# Buggy_Motor_Board.net
KiCad netlist of a schematic drawn in EAGLE
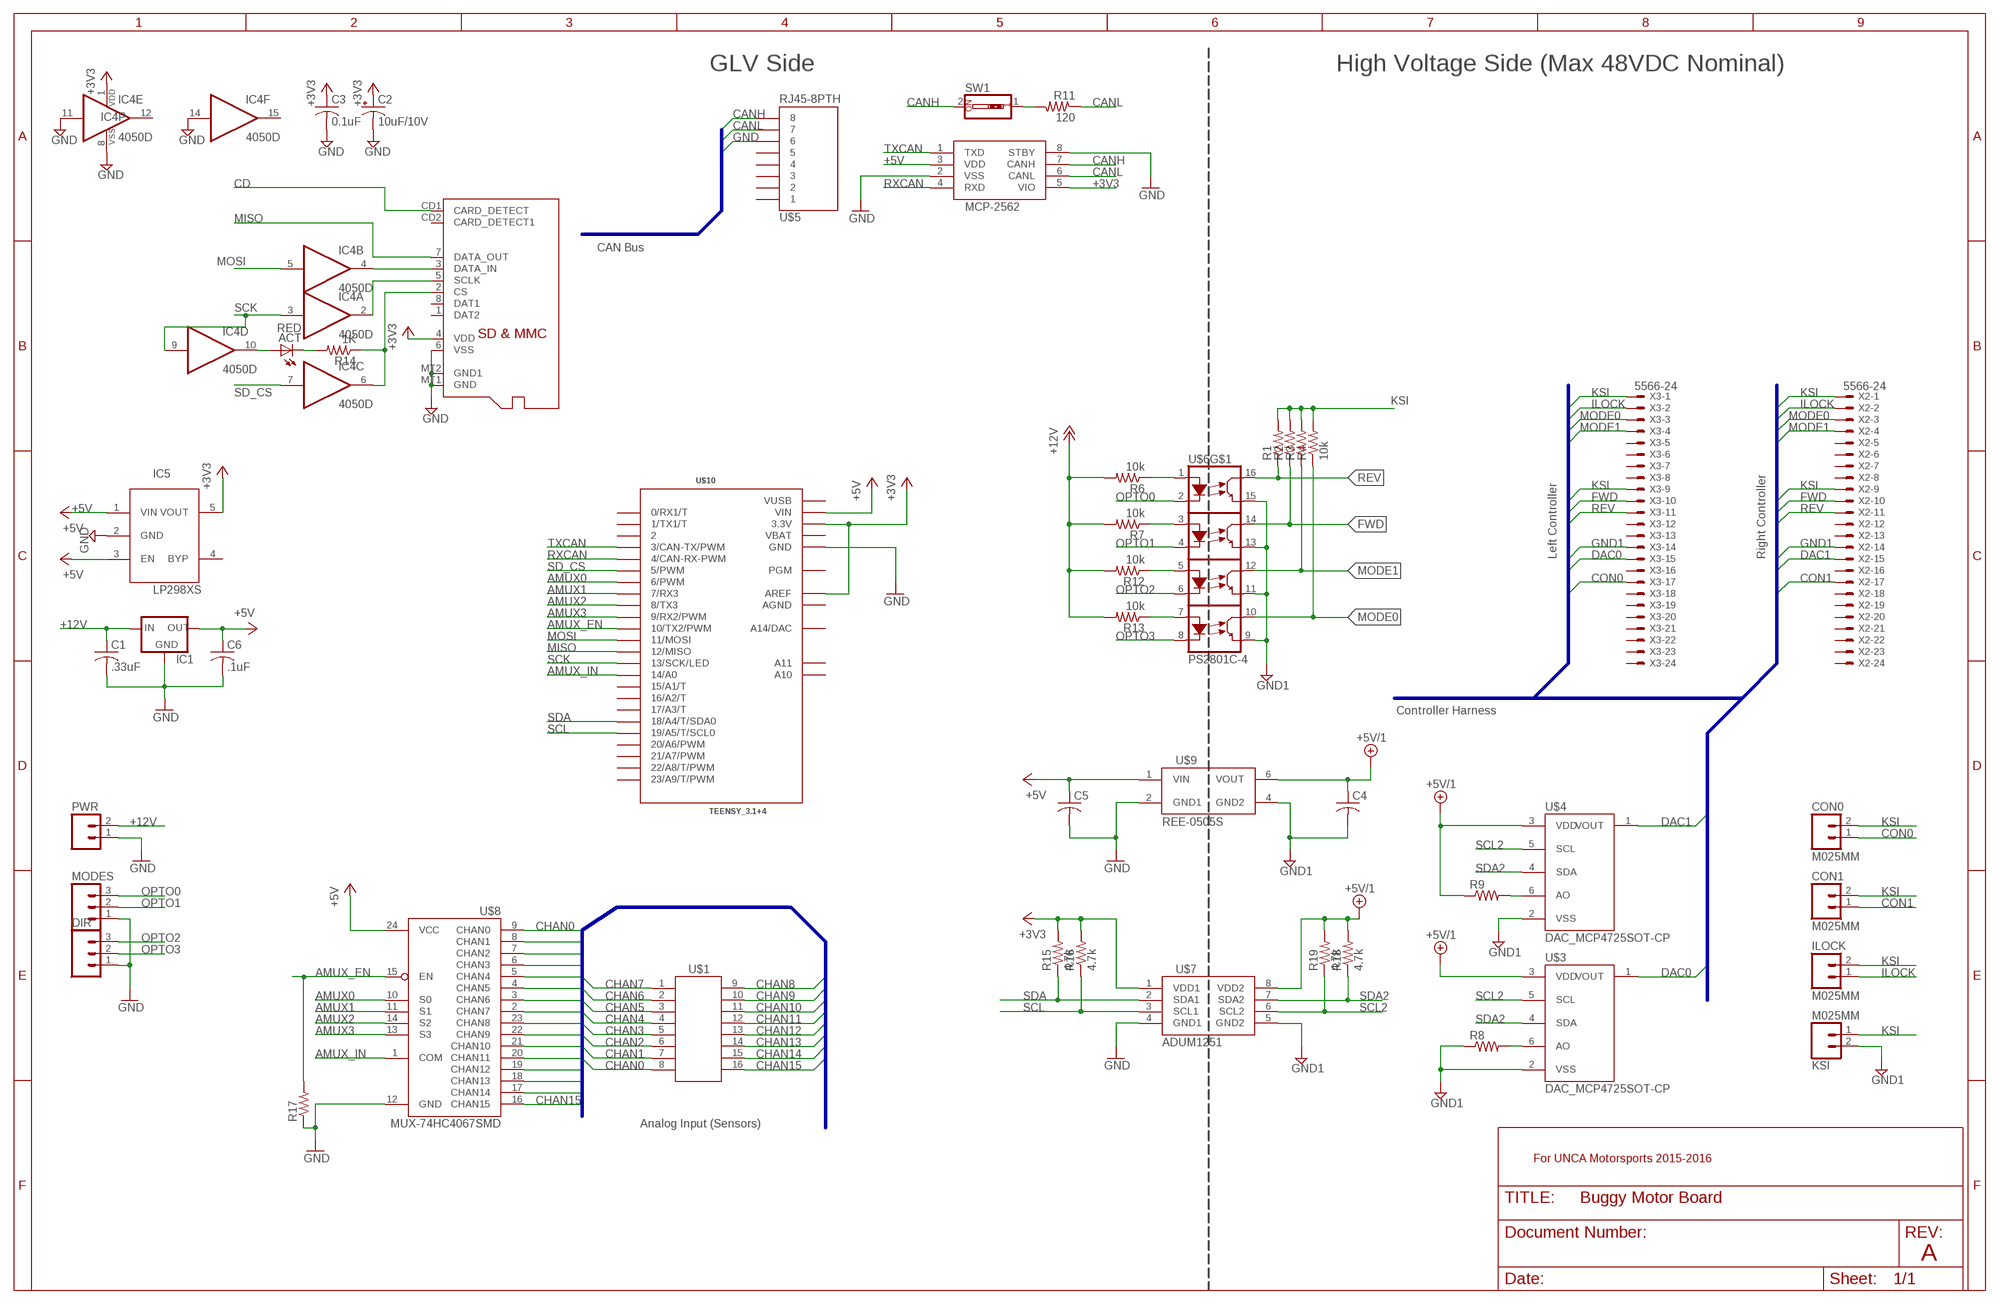
[diagram p0: schematic, sheet 1]

(export (version "E")
  (design (tool "Eeschema 10.0.6"))
  (components
    (comp (ref "ACT")
      (value "RED")
      (footprint "eagle-import:CHIP-LED0805")
      (libsource (lib "eagle-import") (part "LEDCHIP-LED0805"))
    )
    (comp (ref "C1")
      (value ".33uF")
      (footprint "eagle-import:C0805")
      (libsource (lib "eagle-import") (part "rcl_C-USC0805"))
    )
    (comp (ref "C2")
      (value "10uF/10V")
      (footprint "eagle-import:A_3216-18R")
      (libsource (lib "eagle-import") (part "CPOL-USA/3216-18R"))
    )
    (comp (ref "C3")
      (value "0.1uF")
      (footprint "eagle-import:C0805K")
      (libsource (lib "eagle-import") (part "C-USC0805K"))
    )
    (comp (ref "C4")
      (value "C-USC1210K")
      (footprint "eagle-import:C1210K")
      (libsource (lib "eagle-import") (part "rcl_C-USC1210K"))
    )
    (comp (ref "C5")
      (value "C-USC1210K")
      (footprint "eagle-import:C1210K")
      (libsource (lib "eagle-import") (part "rcl_C-USC1210K"))
    )
    (comp (ref "C6")
      (value ".1uF")
      (footprint "eagle-import:C0805")
      (libsource (lib "eagle-import") (part "rcl_C-USC0805"))
    )
    (comp (ref "CON0")
      (value "M025MM")
      (footprint "eagle-import:SCREWTERMINAL-5MM-2")
      (libsource (lib "eagle-import") (part "M025MM"))
    )
    (comp (ref "CON1")
      (value "M025MM")
      (footprint "eagle-import:SCREWTERMINAL-5MM-2")
      (libsource (lib "eagle-import") (part "M025MM"))
    )
    (comp (ref "DIR")
      (value "M03SCREW_LOCK")
      (footprint "eagle-import:SCREWTERMINAL-3.5MM-3_LOCK.007S")
      (libsource (lib "eagle-import") (part "M03SCREW_LOCK"))
    )
    (comp (ref "IC1")
      (value "V_REG_78XXSIDE")
      (footprint "eagle-import:78XXL")
      (libsource (lib "eagle-import") (part "V_REG_78XXSIDE"))
    )
    (comp (ref "IC4")
      (value "4050D")
      (footprint "eagle-import:SO16")
      (libsource (lib "eagle-import") (part "4050D"))
    )
    (comp (ref "IC5")
      (value "LP298XS")
      (footprint "eagle-import:SOT23-5L")
      (libsource (lib "eagle-import") (part "LP298XS"))
    )
    (comp (ref "ILOCK")
      (value "M025MM")
      (footprint "eagle-import:SCREWTERMINAL-5MM-2")
      (libsource (lib "eagle-import") (part "M025MM"))
    )
    (comp (ref "KSI")
      (value "M025MM")
      (footprint "eagle-import:SCREWTERMINAL-5MM-2")
      (libsource (lib "eagle-import") (part "M025MM"))
    )
    (comp (ref "MCP-2562")
      (value "MCP2562")
      (footprint "eagle-import:SO08")
      (libsource (lib "eagle-import") (part "MCP2562"))
    )
    (comp (ref "MODES")
      (value "M03SCREW_LOCK")
      (footprint "eagle-import:SCREWTERMINAL-3.5MM-3_LOCK.007S")
      (libsource (lib "eagle-import") (part "M03SCREW_LOCK"))
    )
    (comp (ref "PWR")
      (value "M023.5MM_LOCK")
      (footprint "eagle-import:SCREWTERMINAL-3.5MM-2_LOCK")
      (libsource (lib "eagle-import") (part "M023.5MM_LOCK"))
    )
    (comp (ref "R1")
      (value "RESISTOR0805-RES")
      (footprint "eagle-import:0805")
      (libsource (lib "eagle-import") (part "RESISTOR0805-RES"))
    )
    (comp (ref "R2")
      (value "RESISTOR0805-RES")
      (footprint "eagle-import:0805")
      (libsource (lib "eagle-import") (part "RESISTOR0805-RES"))
    )
    (comp (ref "R3")
      (value "RESISTOR0805-RES")
      (footprint "eagle-import:0805")
      (libsource (lib "eagle-import") (part "RESISTOR0805-RES"))
    )
    (comp (ref "R4")
      (value "10k")
      (footprint "eagle-import:0805")
      (libsource (lib "eagle-import") (part "RESISTOR0805-RES"))
    )
    (comp (ref "R6")
      (value "10k")
      (footprint "eagle-import:0805")
      (libsource (lib "eagle-import") (part "RESISTOR0805-RES"))
    )
    (comp (ref "R7")
      (value "10k")
      (footprint "eagle-import:0805")
      (libsource (lib "eagle-import") (part "RESISTOR0805-RES"))
    )
    (comp (ref "R8")
      (value "RESISTOR0805-RES")
      (footprint "eagle-import:0805")
      (libsource (lib "eagle-import") (part "RESISTOR0805-RES"))
    )
    (comp (ref "R9")
      (value "RESISTOR0805-RES")
      (footprint "eagle-import:0805")
      (libsource (lib "eagle-import") (part "RESISTOR0805-RES"))
    )
    (comp (ref "R11")
      (value "120")
      (footprint "eagle-import:0805")
      (libsource (lib "eagle-import") (part "RESISTOR0805-RES"))
    )
    (comp (ref "R12")
      (value "10k")
      (footprint "eagle-import:0805")
      (libsource (lib "eagle-import") (part "RESISTOR0805-RES"))
    )
    (comp (ref "R13")
      (value "10k")
      (footprint "eagle-import:0805")
      (libsource (lib "eagle-import") (part "RESISTOR0805-RES"))
    )
    (comp (ref "R14")
      (value "1K")
      (footprint "eagle-import:0805")
      (libsource (lib "eagle-import") (part "RESISTOR0805-RES"))
    )
    (comp (ref "R15")
      (value "4.7k")
      (footprint "eagle-import:0805")
      (libsource (lib "eagle-import") (part "RESISTOR0805-RES"))
    )
    (comp (ref "R16")
      (value "4.7k")
      (footprint "eagle-import:0805")
      (libsource (lib "eagle-import") (part "RESISTOR0805-RES"))
    )
    (comp (ref "R17")
      (value "RESISTOR0805-RES")
      (footprint "eagle-import:0805")
      (libsource (lib "eagle-import") (part "RESISTOR0805-RES"))
    )
    (comp (ref "R18")
      (value "4.7k")
      (footprint "eagle-import:0805")
      (libsource (lib "eagle-import") (part "RESISTOR0805-RES"))
    )
    (comp (ref "R19")
      (value "4.7k")
      (footprint "eagle-import:0805")
      (libsource (lib "eagle-import") (part "RESISTOR0805-RES"))
    )
    (comp (ref "SW1")
      (value "SW_DIP-1")
      (footprint "eagle-import:EDG-01")
      (libsource (lib "eagle-import") (part "SW_DIP-1"))
    )
    (comp (ref "U$1")
      (value "WM9300")
      (footprint "eagle-import:WM9300")
      (libsource (lib "eagle-import") (part "WM9300"))
    )
    (comp (ref "U$3")
      (value "DAC_MCP4725SOT-CP")
      (footprint "eagle-import:SOT23-6-MCP4725")
      (libsource (lib "eagle-import") (part "DAC_MCP4725SOT-CP"))
    )
    (comp (ref "U$4")
      (value "DAC_MCP4725SOT-CP")
      (footprint "eagle-import:SOT23-6-MCP4725")
      (libsource (lib "eagle-import") (part "DAC_MCP4725SOT-CP"))
    )
    (comp (ref "U$5")
      (value "RJ45-8PTH")
      (footprint "eagle-import:RJ45-8")
      (libsource (lib "eagle-import") (part "RJ45-8PTH"))
    )
    (comp (ref "U$6")
      (value "PS2801C-4")
      (footprint "eagle-import:16-SOIC")
      (libsource (lib "eagle-import") (part "PS2801C-4"))
    )
    (comp (ref "U$7")
      (value "ADUM1251")
      (footprint "eagle-import:8-SOIC")
      (libsource (lib "eagle-import") (part "ADUM1251"))
    )
    (comp (ref "U$8")
      (value "MUX-74HC4067SMD")
      (footprint "eagle-import:SSOP24")
      (libsource (lib "eagle-import") (part "MUX-74HC4067SMD"))
    )
    (comp (ref "U$9")
      (value "REE-0505S")
      (footprint "eagle-import:REE-0505S")
      (libsource (lib "eagle-import") (part "REE-0505S"))
    )
    (comp (ref "U$10")
      (value "TEENSY_3.1+4")
      (footprint "eagle-import:TEENSY_3.1+4")
      (libsource (lib "eagle-import") (part "TEENSY_3.1+4"))
    )
    (comp (ref "X1")
      (value "MICROSD")
      (footprint "eagle-import:MICROSD")
      (libsource (lib "eagle-import") (part "MICROSD"))
    )
    (comp (ref "X2")
      (value "5566-24")
      (footprint "eagle-import:5566-24")
      (libsource (lib "eagle-import") (part "5566-24"))
    )
    (comp (ref "X3")
      (value "5566-24")
      (footprint "eagle-import:5566-24")
      (libsource (lib "eagle-import") (part "5566-24"))
    )
  )
  (nets
    (net (code "1") (name "+3V3") (class "Default")
      (node (ref "C2") (pin "+") (pinfunction "+_+") (pintype "passive"))
      (node (ref "C3") (pin "1") (pinfunction "1_1") (pintype "passive"))
      (node (ref "IC4") (pin "1") (pinfunction "VDD_1") (pintype "power_in"))
      (node (ref "IC5") (pin "5") (pinfunction "VOUT_5") (pintype "bidirectional"))
      (node (ref "MCP-2562") (pin "5") (pinfunction "VIO_5") (pintype "bidirectional"))
      (node (ref "R15") (pin "2") (pinfunction "2_2") (pintype "passive"))
      (node (ref "R16") (pin "2") (pinfunction "2_2") (pintype "passive"))
      (node (ref "U$10") (pin "3.3V") (pinfunction "3.3V_3.3V") (pintype "power_in"))
      (node (ref "U$10") (pin "3.3V1") (pinfunction "3.3V_3.3V1") (pintype "power_in"))
      (node (ref "U$10") (pin "AREF") (pinfunction "AREF_AREF") (pintype "power_in"))
      (node (ref "U$7") (pin "1") (pinfunction "VDD1_1") (pintype "bidirectional"))
      (node (ref "X1") (pin "4") (pinfunction "VDD_4") (pintype "power_in"))
    )
    (net (code "2") (name "+5V") (class "Default")
      (node (ref "C5") (pin "1") (pinfunction "1_1") (pintype "passive"))
      (node (ref "C6") (pin "1") (pinfunction "1_1") (pintype "passive"))
      (node (ref "IC1") (pin "OUT") (pinfunction "OUT_OUT") (pintype "output"))
      (node (ref "IC5") (pin "1") (pinfunction "VIN_1") (pintype "bidirectional"))
      (node (ref "IC5") (pin "3") (pinfunction "EN_3") (pintype "bidirectional"))
      (node (ref "MCP-2562") (pin "3") (pinfunction "VDD_3") (pintype "bidirectional"))
      (node (ref "U$10") (pin "VIN") (pinfunction "VIN_VIN") (pintype "power_in"))
      (node (ref "U$8") (pin "24") (pinfunction "VCC_24") (pintype "bidirectional"))
      (node (ref "U$9") (pin "1") (pinfunction "VIN_1") (pintype "bidirectional"))
    )
    (net (code "3") (name "+5V{slash}1") (class "Default")
      (node (ref "C4") (pin "1") (pinfunction "1_1") (pintype "passive"))
      (node (ref "R18") (pin "2") (pinfunction "2_2") (pintype "passive"))
      (node (ref "R19") (pin "2") (pinfunction "2_2") (pintype "passive"))
      (node (ref "R9") (pin "1") (pinfunction "1_1") (pintype "passive"))
      (node (ref "U$3") (pin "3") (pinfunction "VDD_3") (pintype "bidirectional"))
      (node (ref "U$4") (pin "3") (pinfunction "VDD_3") (pintype "bidirectional"))
      (node (ref "U$7") (pin "8") (pinfunction "VDD2_8") (pintype "bidirectional"))
      (node (ref "U$9") (pin "6") (pinfunction "VOUT_6") (pintype "bidirectional"))
    )
    (net (code "4") (name "+12V") (class "Default")
      (node (ref "C1") (pin "1") (pinfunction "1_1") (pintype "passive"))
      (node (ref "IC1") (pin "IN") (pinfunction "IN_IN") (pintype "input"))
      (node (ref "PWR") (pin "2") (pinfunction "2_2") (pintype "passive"))
      (node (ref "R12") (pin "2") (pinfunction "2_2") (pintype "passive"))
      (node (ref "R13") (pin "2") (pinfunction "2_2") (pintype "passive"))
      (node (ref "R6") (pin "2") (pinfunction "2_2") (pintype "passive"))
      (node (ref "R7") (pin "2") (pinfunction "2_2") (pintype "passive"))
    )
    (net (code "5") (name "/AGND") (class "Default")
      (node (ref "U$10") (pin "AGND") (pinfunction "AGND_AGND") (pintype "power_in"))
    )
    (net (code "6") (name "/AMUX0") (class "Default")
      (node (ref "U$10") (pin "6") (pinfunction "6/PWM_6") (pintype "bidirectional"))
      (node (ref "U$8") (pin "10") (pinfunction "S0_10") (pintype "input"))
    )
    (net (code "7") (name "/AMUX1") (class "Default")
      (node (ref "U$10") (pin "7") (pinfunction "7/RX3_7") (pintype "bidirectional"))
      (node (ref "U$8") (pin "11") (pinfunction "S1_11") (pintype "input"))
    )
    (net (code "8") (name "/AMUX2") (class "Default")
      (node (ref "U$10") (pin "8") (pinfunction "8/TX3_8") (pintype "bidirectional"))
      (node (ref "U$8") (pin "14") (pinfunction "S2_14") (pintype "input"))
    )
    (net (code "9") (name "/AMUX3") (class "Default")
      (node (ref "U$10") (pin "9") (pinfunction "9/RX2/PWM_9") (pintype "bidirectional"))
      (node (ref "U$8") (pin "13") (pinfunction "S3_13") (pintype "input"))
    )
    (net (code "10") (name "/AMUX_EN") (class "Default")
      (node (ref "R17") (pin "2") (pinfunction "2_2") (pintype "passive"))
      (node (ref "U$10") (pin "10") (pinfunction "10/TX2/PWM_10") (pintype "bidirectional"))
      (node (ref "U$8") (pin "15") (pinfunction "EN_15") (pintype "input"))
    )
    (net (code "11") (name "/AMUX_IN") (class "Default")
      (node (ref "U$10") (pin "14/A0") (pinfunction "14/A0_14/A0") (pintype "bidirectional"))
      (node (ref "U$8") (pin "1") (pinfunction "COM_1") (pintype "bidirectional"))
    )
    (net (code "12") (name "/CANH") (class "Default")
      (node (ref "MCP-2562") (pin "7") (pinfunction "CANH_7") (pintype "bidirectional"))
      (node (ref "SW1") (pin "2") (pinfunction "2_2") (pintype "passive"))
      (node (ref "U$5") (pin "8") (pinfunction "8_8") (pintype "bidirectional"))
    )
    (net (code "13") (name "/CANL") (class "Default")
      (node (ref "MCP-2562") (pin "6") (pinfunction "CANL_6") (pintype "bidirectional"))
      (node (ref "R11") (pin "1") (pinfunction "1_1") (pintype "passive"))
      (node (ref "U$5") (pin "7") (pinfunction "7_7") (pintype "bidirectional"))
    )
    (net (code "14") (name "/CD") (class "Default")
      (node (ref "X1") (pin "CD1") (pinfunction "CARD_DETECT_CD1") (pintype "passive"))
    )
    (net (code "15") (name "/CHAN0") (class "Default")
      (node (ref "U$1") (pin "8") (pinfunction "P$8_8") (pintype "bidirectional"))
      (node (ref "U$8") (pin "9") (pinfunction "CHAN0_9") (pintype "bidirectional"))
    )
    (net (code "16") (name "/CHAN1") (class "Default")
      (node (ref "U$1") (pin "7") (pinfunction "P$7_7") (pintype "bidirectional"))
      (node (ref "U$8") (pin "8") (pinfunction "CHAN1_8") (pintype "bidirectional"))
    )
    (net (code "17") (name "/CHAN2") (class "Default")
      (node (ref "U$1") (pin "6") (pinfunction "P$6_6") (pintype "bidirectional"))
      (node (ref "U$8") (pin "7") (pinfunction "CHAN2_7") (pintype "bidirectional"))
    )
    (net (code "18") (name "/CHAN3") (class "Default")
      (node (ref "U$1") (pin "5") (pinfunction "P$5_5") (pintype "bidirectional"))
      (node (ref "U$8") (pin "6") (pinfunction "CHAN3_6") (pintype "bidirectional"))
    )
    (net (code "19") (name "/CHAN4") (class "Default")
      (node (ref "U$1") (pin "4") (pinfunction "P$4_4") (pintype "bidirectional"))
      (node (ref "U$8") (pin "5") (pinfunction "CHAN4_5") (pintype "bidirectional"))
    )
    (net (code "20") (name "/CHAN5") (class "Default")
      (node (ref "U$1") (pin "3") (pinfunction "P$3_3") (pintype "bidirectional"))
      (node (ref "U$8") (pin "4") (pinfunction "CHAN5_4") (pintype "bidirectional"))
    )
    (net (code "21") (name "/CHAN6") (class "Default")
      (node (ref "U$1") (pin "2") (pinfunction "P$2_2") (pintype "bidirectional"))
      (node (ref "U$8") (pin "3") (pinfunction "CHAN6_3") (pintype "bidirectional"))
    )
    (net (code "22") (name "/CHAN7") (class "Default")
      (node (ref "U$1") (pin "1") (pinfunction "P$1_1") (pintype "bidirectional"))
      (node (ref "U$8") (pin "2") (pinfunction "CHAN7_2") (pintype "bidirectional"))
    )
    (net (code "23") (name "/CHAN8") (class "Default")
      (node (ref "U$1") (pin "9") (pinfunction "P$9_9") (pintype "bidirectional"))
      (node (ref "U$8") (pin "23") (pinfunction "CHAN8_23") (pintype "bidirectional"))
    )
    (net (code "24") (name "/CHAN9") (class "Default")
      (node (ref "U$1") (pin "10") (pinfunction "P$10_10") (pintype "bidirectional"))
      (node (ref "U$8") (pin "22") (pinfunction "CHAN9_22") (pintype "bidirectional"))
    )
    (net (code "25") (name "/CHAN10") (class "Default")
      (node (ref "U$1") (pin "11") (pinfunction "P$11_11") (pintype "bidirectional"))
      (node (ref "U$8") (pin "21") (pinfunction "CHAN10_21") (pintype "bidirectional"))
    )
    (net (code "26") (name "/CHAN11") (class "Default")
      (node (ref "U$1") (pin "12") (pinfunction "P$12_12") (pintype "bidirectional"))
      (node (ref "U$8") (pin "20") (pinfunction "CHAN11_20") (pintype "bidirectional"))
    )
    (net (code "27") (name "/CHAN12") (class "Default")
      (node (ref "U$1") (pin "13") (pinfunction "P$13_13") (pintype "bidirectional"))
      (node (ref "U$8") (pin "19") (pinfunction "CHAN12_19") (pintype "bidirectional"))
    )
    (net (code "28") (name "/CHAN13") (class "Default")
      (node (ref "U$1") (pin "14") (pinfunction "P$14_14") (pintype "bidirectional"))
      (node (ref "U$8") (pin "18") (pinfunction "CHAN13_18") (pintype "bidirectional"))
    )
    (net (code "29") (name "/CHAN14") (class "Default")
      (node (ref "U$1") (pin "15") (pinfunction "P$15_15") (pintype "bidirectional"))
      (node (ref "U$8") (pin "17") (pinfunction "CHAN14_17") (pintype "bidirectional"))
    )
    (net (code "30") (name "/CHAN15") (class "Default")
      (node (ref "U$1") (pin "16") (pinfunction "P$16_16") (pintype "bidirectional"))
      (node (ref "U$8") (pin "16") (pinfunction "CHAN15_16") (pintype "bidirectional"))
    )
    (net (code "31") (name "/CON0") (class "Default")
      (node (ref "CON0") (pin "1") (pinfunction "1_1") (pintype "passive"))
      (node (ref "X3") (pin "17") (pinfunction "S_17") (pintype "passive"))
    )
    (net (code "32") (name "/CON1") (class "Default")
      (node (ref "CON1") (pin "1") (pinfunction "1_1") (pintype "passive"))
      (node (ref "X2") (pin "17") (pinfunction "S_17") (pintype "passive"))
    )
    (net (code "33") (name "/DAC0") (class "Default")
      (node (ref "U$3") (pin "1") (pinfunction "VOUT_1") (pintype "bidirectional"))
      (node (ref "X3") (pin "15") (pinfunction "S_15") (pintype "passive"))
    )
    (net (code "34") (name "/DAC1") (class "Default")
      (node (ref "U$4") (pin "1") (pinfunction "VOUT_1") (pintype "bidirectional"))
      (node (ref "X2") (pin "15") (pinfunction "S_15") (pintype "passive"))
    )
    (net (code "35") (name "/ILOCK") (class "Default")
      (node (ref "ILOCK") (pin "1") (pinfunction "1_1") (pintype "passive"))
      (node (ref "X2") (pin "2") (pinfunction "S_2") (pintype "passive"))
      (node (ref "X3") (pin "2") (pinfunction "S_2") (pintype "passive"))
    )
    (net (code "36") (name "/KSI") (class "Default")
      (node (ref "CON0") (pin "2") (pinfunction "2_2") (pintype "passive"))
      (node (ref "CON1") (pin "2") (pinfunction "2_2") (pintype "passive"))
      (node (ref "ILOCK") (pin "2") (pinfunction "2_2") (pintype "passive"))
      (node (ref "KSI") (pin "1") (pinfunction "1_1") (pintype "passive"))
      (node (ref "R1") (pin "2") (pinfunction "2_2") (pintype "passive"))
      (node (ref "R2") (pin "2") (pinfunction "2_2") (pintype "passive"))
      (node (ref "R3") (pin "2") (pinfunction "2_2") (pintype "passive"))
      (node (ref "R4") (pin "2") (pinfunction "2_2") (pintype "passive"))
      (node (ref "X2") (pin "1") (pinfunction "S_1") (pintype "passive"))
      (node (ref "X2") (pin "9") (pinfunction "S_9") (pintype "passive"))
      (node (ref "X3") (pin "1") (pinfunction "S_1") (pintype "passive"))
      (node (ref "X3") (pin "9") (pinfunction "S_9") (pintype "passive"))
    )
    (net (code "37") (name "/MISO") (class "Default")
      (node (ref "U$10") (pin "12") (pinfunction "12/MISO_12") (pintype "bidirectional"))
      (node (ref "X1") (pin "7") (pinfunction "DATA_OUT_7") (pintype "output"))
    )
    (net (code "38") (name "/MOSI") (class "Default")
      (node (ref "IC4") (pin "5") (pinfunction "I_5") (pintype "input"))
      (node (ref "U$10") (pin "11") (pinfunction "11/MOSI_11") (pintype "bidirectional"))
    )
    (net (code "39") (name "/OPTO0") (class "Default")
      (node (ref "MODES") (pin "3") (pinfunction "3_3") (pintype "passive"))
      (node (ref "U$6") (pin "2") (pinfunction "C_2") (pintype "passive"))
    )
    (net (code "40") (name "/OPTO1") (class "Default")
      (node (ref "MODES") (pin "2") (pinfunction "2_2") (pintype "passive"))
      (node (ref "U$6") (pin "4") (pinfunction "C_4") (pintype "passive"))
    )
    (net (code "41") (name "/OPTO2") (class "Default")
      (node (ref "DIR") (pin "3") (pinfunction "3_3") (pintype "passive"))
      (node (ref "U$6") (pin "6") (pinfunction "C_6") (pintype "passive"))
    )
    (net (code "42") (name "/OPTO3") (class "Default")
      (node (ref "DIR") (pin "2") (pinfunction "2_2") (pintype "passive"))
      (node (ref "U$6") (pin "8") (pinfunction "C_8") (pintype "passive"))
    )
    (net (code "43") (name "/RXCAN") (class "Default")
      (node (ref "MCP-2562") (pin "4") (pinfunction "RXD_4") (pintype "bidirectional"))
      (node (ref "U$10") (pin "4") (pinfunction "4/CAN-RX-PWM_4") (pintype "bidirectional"))
    )
    (net (code "44") (name "/SCK") (class "Default")
      (node (ref "IC4") (pin "3") (pinfunction "I_3") (pintype "input"))
      (node (ref "IC4") (pin "9") (pinfunction "I_9") (pintype "input"))
      (node (ref "U$10") (pin "13") (pinfunction "13/SCK/LED_13") (pintype "bidirectional"))
    )
    (net (code "45") (name "/SCL") (class "Default")
      (node (ref "R16") (pin "1") (pinfunction "1_1") (pintype "passive"))
      (node (ref "U$10") (pin "19/A5") (pinfunction "19/A5/T/SCL0_19/A5") (pintype "bidirectional"))
      (node (ref "U$7") (pin "3") (pinfunction "SCL1_3") (pintype "bidirectional"))
    )
    (net (code "46") (name "/SCL2") (class "Default")
      (node (ref "R19") (pin "1") (pinfunction "1_1") (pintype "passive"))
      (node (ref "U$3") (pin "5") (pinfunction "SCL_5") (pintype "bidirectional"))
      (node (ref "U$4") (pin "5") (pinfunction "SCL_5") (pintype "bidirectional"))
      (node (ref "U$7") (pin "6") (pinfunction "SCL2_6") (pintype "bidirectional"))
    )
    (net (code "47") (name "/SDA") (class "Default")
      (node (ref "R15") (pin "1") (pinfunction "1_1") (pintype "passive"))
      (node (ref "U$10") (pin "18/A4") (pinfunction "18/A4/T/SDA0_18/A4") (pintype "bidirectional"))
      (node (ref "U$7") (pin "2") (pinfunction "SDA1_2") (pintype "bidirectional"))
    )
    (net (code "48") (name "/SDA2") (class "Default")
      (node (ref "R18") (pin "1") (pinfunction "1_1") (pintype "passive"))
      (node (ref "U$3") (pin "4") (pinfunction "SDA_4") (pintype "bidirectional"))
      (node (ref "U$4") (pin "4") (pinfunction "SDA_4") (pintype "bidirectional"))
      (node (ref "U$7") (pin "7") (pinfunction "SDA2_7") (pintype "bidirectional"))
    )
    (net (code "49") (name "/SD_CS") (class "Default")
      (node (ref "IC4") (pin "7") (pinfunction "I_7") (pintype "input"))
      (node (ref "U$10") (pin "5") (pinfunction "5/PWM_5") (pintype "bidirectional"))
    )
    (net (code "50") (name "/TXCAN") (class "Default")
      (node (ref "MCP-2562") (pin "1") (pinfunction "TXD_1") (pintype "bidirectional"))
      (node (ref "U$10") (pin "3") (pinfunction "3/CAN-TX/PWM_3") (pintype "bidirectional"))
    )
    (net (code "51") (name "/VBAT") (class "Default")
      (node (ref "U$10") (pin "VBAT") (pinfunction "VBAT_VBAT") (pintype "power_in"))
    )
    (net (code "52") (name "/VUSB") (class "Default")
      (node (ref "U$10") (pin "VUSB") (pinfunction "VUSB_VUSB") (pintype "power_in"))
    )
    (net (code "53") (name "FWD") (class "Default")
      (node (ref "R2") (pin "1") (pinfunction "1_1") (pintype "passive"))
      (node (ref "U$6") (pin "14") (pinfunction "L1_14") (pintype "passive"))
      (node (ref "X2") (pin "10") (pinfunction "S_10") (pintype "passive"))
      (node (ref "X3") (pin "10") (pinfunction "S_10") (pintype "passive"))
    )
    (net (code "54") (name "GND") (class "Default")
      (node (ref "C1") (pin "2") (pinfunction "2_2") (pintype "passive"))
      (node (ref "C2") (pin "-") (pinfunction "-_-") (pintype "passive"))
      (node (ref "C3") (pin "2") (pinfunction "2_2") (pintype "passive"))
      (node (ref "C5") (pin "2") (pinfunction "2_2") (pintype "passive"))
      (node (ref "C6") (pin "2") (pinfunction "2_2") (pintype "passive"))
      (node (ref "DIR") (pin "1") (pinfunction "1_1") (pintype "passive"))
      (node (ref "IC1") (pin "GND") (pinfunction "GND_GND") (pintype "input"))
      (node (ref "IC4") (pin "11") (pinfunction "I_11") (pintype "input"))
      (node (ref "IC4") (pin "14") (pinfunction "I_14") (pintype "input"))
      (node (ref "IC4") (pin "8") (pinfunction "VSS_8") (pintype "power_in"))
      (node (ref "IC5") (pin "2") (pinfunction "GND_2") (pintype "bidirectional"))
      (node (ref "MCP-2562") (pin "2") (pinfunction "VSS_2") (pintype "bidirectional"))
      (node (ref "MCP-2562") (pin "8") (pinfunction "STBY_8") (pintype "bidirectional"))
      (node (ref "MODES") (pin "1") (pinfunction "1_1") (pintype "passive"))
      (node (ref "PWR") (pin "1") (pinfunction "1_1") (pintype "passive"))
      (node (ref "R17") (pin "1") (pinfunction "1_1") (pintype "passive"))
      (node (ref "U$10") (pin "GND") (pinfunction "GND_GND") (pintype "power_in"))
      (node (ref "U$10") (pin "GND1") (pinfunction "GND_GND1") (pintype "power_in"))
      (node (ref "U$5") (pin "6") (pinfunction "6_6") (pintype "bidirectional"))
      (node (ref "U$7") (pin "4") (pinfunction "GND1_4") (pintype "bidirectional"))
      (node (ref "U$8") (pin "12") (pinfunction "GND_12") (pintype "bidirectional"))
      (node (ref "U$9") (pin "2") (pinfunction "GND1_2") (pintype "bidirectional"))
      (node (ref "X1") (pin "6") (pinfunction "VSS_6") (pintype "power_in"))
      (node (ref "X1") (pin "MT1") (pinfunction "GND_MT1") (pintype "power_in"))
      (node (ref "X1") (pin "MT2") (pinfunction "GND1_MT2") (pintype "power_in"))
    )
    (net (code "55") (name "GND1") (class "Default")
      (node (ref "C4") (pin "2") (pinfunction "2_2") (pintype "passive"))
      (node (ref "KSI") (pin "2") (pinfunction "2_2") (pintype "passive"))
      (node (ref "R8") (pin "1") (pinfunction "1_1") (pintype "passive"))
      (node (ref "U$3") (pin "2") (pinfunction "VSS_2") (pintype "bidirectional"))
      (node (ref "U$4") (pin "2") (pinfunction "VSS_2") (pintype "bidirectional"))
      (node (ref "U$6") (pin "11") (pinfunction "L2_11") (pintype "passive"))
      (node (ref "U$6") (pin "13") (pinfunction "L2_13") (pintype "passive"))
      (node (ref "U$6") (pin "15") (pinfunction "L2_15") (pintype "passive"))
      (node (ref "U$6") (pin "9") (pinfunction "L2_9") (pintype "passive"))
      (node (ref "U$7") (pin "5") (pinfunction "GND2_5") (pintype "bidirectional"))
      (node (ref "U$9") (pin "4") (pinfunction "GND2_4") (pintype "bidirectional"))
      (node (ref "X2") (pin "14") (pinfunction "S_14") (pintype "passive"))
      (node (ref "X3") (pin "14") (pinfunction "S_14") (pintype "passive"))
    )
    (net (code "56") (name "MODE0") (class "Default")
      (node (ref "R4") (pin "1") (pinfunction "1_1") (pintype "passive"))
      (node (ref "U$6") (pin "10") (pinfunction "L1_10") (pintype "passive"))
      (node (ref "X2") (pin "3") (pinfunction "S_3") (pintype "passive"))
      (node (ref "X3") (pin "3") (pinfunction "S_3") (pintype "passive"))
    )
    (net (code "57") (name "MODE1") (class "Default")
      (node (ref "R3") (pin "1") (pinfunction "1_1") (pintype "passive"))
      (node (ref "U$6") (pin "12") (pinfunction "L1_12") (pintype "passive"))
      (node (ref "X2") (pin "4") (pinfunction "S_4") (pintype "passive"))
      (node (ref "X3") (pin "4") (pinfunction "S_4") (pintype "passive"))
    )
    (net (code "58") (name "Net-(ACT-PadC)") (class "Default")
      (node (ref "ACT") (pin "C") (pinfunction "C_C") (pintype "passive"))
      (node (ref "R14") (pin "2") (pinfunction "2_2") (pintype "passive"))
    )
    (net (code "59") (name "Net-(IC4A-O)") (class "Default")
      (node (ref "IC4") (pin "2") (pinfunction "O_2") (pintype "output"))
      (node (ref "X1") (pin "5") (pinfunction "SCLK_5") (pintype "input"))
    )
    (net (code "60") (name "Net-(IC4B-O)") (class "Default")
      (node (ref "IC4") (pin "4") (pinfunction "O_4") (pintype "output"))
      (node (ref "X1") (pin "3") (pinfunction "DATA_IN_3") (pintype "input"))
    )
    (net (code "61") (name "Net-(IC4C-O)") (class "Default")
      (node (ref "IC4") (pin "6") (pinfunction "O_6") (pintype "output"))
      (node (ref "R14") (pin "1") (pinfunction "1_1") (pintype "passive"))
      (node (ref "X1") (pin "2") (pinfunction "CS_2") (pintype "input"))
    )
    (net (code "62") (name "Net-(IC4D-O)") (class "Default")
      (node (ref "ACT") (pin "A") (pinfunction "A_A") (pintype "passive"))
      (node (ref "IC4") (pin "10") (pinfunction "O_10") (pintype "output"))
    )
    (net (code "63") (name "Net-(R11-Pad2)") (class "Default")
      (node (ref "R11") (pin "2") (pinfunction "2_2") (pintype "passive"))
      (node (ref "SW1") (pin "1") (pinfunction "1_1") (pintype "passive"))
    )
    (net (code "64") (name "Net-(U$3-AO)") (class "Default")
      (node (ref "R8") (pin "2") (pinfunction "2_2") (pintype "passive"))
      (node (ref "U$3") (pin "6") (pinfunction "AO_6") (pintype "bidirectional"))
    )
    (net (code "65") (name "Net-(U$4-AO)") (class "Default")
      (node (ref "R9") (pin "2") (pinfunction "2_2") (pintype "passive"))
      (node (ref "U$4") (pin "6") (pinfunction "AO_6") (pintype "bidirectional"))
    )
    (net (code "66") (name "Net-(U$6A-A)") (class "Default")
      (node (ref "R6") (pin "1") (pinfunction "1_1") (pintype "passive"))
      (node (ref "U$6") (pin "1") (pinfunction "A_1") (pintype "passive"))
    )
    (net (code "67") (name "Net-(U$6B-A)") (class "Default")
      (node (ref "R7") (pin "1") (pinfunction "1_1") (pintype "passive"))
      (node (ref "U$6") (pin "3") (pinfunction "A_3") (pintype "passive"))
    )
    (net (code "68") (name "Net-(U$6C-A)") (class "Default")
      (node (ref "R12") (pin "1") (pinfunction "1_1") (pintype "passive"))
      (node (ref "U$6") (pin "5") (pinfunction "A_5") (pintype "passive"))
    )
    (net (code "69") (name "Net-(U$6D-A)") (class "Default")
      (node (ref "R13") (pin "1") (pinfunction "1_1") (pintype "passive"))
      (node (ref "U$6") (pin "7") (pinfunction "A_7") (pintype "passive"))
    )
    (net (code "70") (name "REV") (class "Default")
      (node (ref "R1") (pin "1") (pinfunction "1_1") (pintype "passive"))
      (node (ref "U$6") (pin "16") (pinfunction "L1_16") (pintype "passive"))
      (node (ref "X2") (pin "11") (pinfunction "S_11") (pintype "passive"))
      (node (ref "X3") (pin "11") (pinfunction "S_11") (pintype "passive"))
    )
    (net (code "71") (name "unconnected-(IC4E-O-Pad12)") (class "Default")
      (node (ref "IC4") (pin "12") (pinfunction "O_12") (pintype "output"))
    )
    (net (code "72") (name "unconnected-(IC4F-O-Pad15)") (class "Default")
      (node (ref "IC4") (pin "15") (pinfunction "O_15") (pintype "output"))
    )
    (net (code "73") (name "unconnected-(IC5-BYP-Pad4)") (class "Default")
      (node (ref "IC5") (pin "4") (pinfunction "BYP_4") (pintype "bidirectional"))
    )
    (net (code "74") (name "unconnected-(U$5-Pad1)") (class "Default")
      (node (ref "U$5") (pin "1") (pinfunction "1_1") (pintype "bidirectional"))
    )
    (net (code "75") (name "unconnected-(U$5-Pad2)") (class "Default")
      (node (ref "U$5") (pin "2") (pinfunction "2_2") (pintype "bidirectional"))
    )
    (net (code "76") (name "unconnected-(U$5-Pad3)") (class "Default")
      (node (ref "U$5") (pin "3") (pinfunction "3_3") (pintype "bidirectional"))
    )
    (net (code "77") (name "unconnected-(U$5-Pad4)") (class "Default")
      (node (ref "U$5") (pin "4") (pinfunction "4_4") (pintype "bidirectional"))
    )
    (net (code "78") (name "unconnected-(U$5-Pad5)") (class "Default")
      (node (ref "U$5") (pin "5") (pinfunction "5_5") (pintype "bidirectional"))
    )
    (net (code "79") (name "unconnected-(U$10-0{slash}RX1{slash}T-Pad0)") (class "Default")
      (node (ref "U$10") (pin "0") (pinfunction "0/RX1/T_0") (pintype "bidirectional"))
    )
    (net (code "80") (name "unconnected-(U$10-1{slash}TX1{slash}T-Pad1)") (class "Default")
      (node (ref "U$10") (pin "1") (pinfunction "1/TX1/T_1") (pintype "bidirectional"))
    )
    (net (code "81") (name "unconnected-(U$10-15{slash}A1{slash}T-Pad15{slash}A1)") (class "Default")
      (node (ref "U$10") (pin "15/A1") (pinfunction "15/A1/T_15/A1") (pintype "bidirectional"))
    )
    (net (code "82") (name "unconnected-(U$10-16{slash}A2{slash}T-Pad16{slash}A2)") (class "Default")
      (node (ref "U$10") (pin "16/A2") (pinfunction "16/A2/T_16/A2") (pintype "bidirectional"))
    )
    (net (code "83") (name "unconnected-(U$10-17{slash}A3{slash}T-Pad17{slash}A3)") (class "Default")
      (node (ref "U$10") (pin "17/A3") (pinfunction "17/A3/T_17/A3") (pintype "bidirectional"))
    )
    (net (code "84") (name "unconnected-(U$10-20{slash}A6{slash}PWM-Pad20{slash}A6)") (class "Default")
      (node (ref "U$10") (pin "20/A6") (pinfunction "20/A6/PWM_20/A6") (pintype "bidirectional"))
    )
    (net (code "85") (name "unconnected-(U$10-21{slash}A7{slash}PWM-Pad21{slash}A7)") (class "Default")
      (node (ref "U$10") (pin "21/A7") (pinfunction "21/A7/PWM_21/A7") (pintype "bidirectional"))
    )
    (net (code "86") (name "unconnected-(U$10-22{slash}A8{slash}T{slash}PWM-Pad22{slash}A8)") (class "Default")
      (node (ref "U$10") (pin "22/A8") (pinfunction "22/A8/T/PWM_22/A8") (pintype "bidirectional"))
    )
    (net (code "87") (name "unconnected-(U$10-23{slash}A9{slash}T{slash}PWM-Pad23{slash}A9)") (class "Default")
      (node (ref "U$10") (pin "23/A9") (pinfunction "23/A9/T/PWM_23/A9") (pintype "bidirectional"))
    )
    (net (code "88") (name "unconnected-(U$10-A14{slash}DAC-PadA14)") (class "Default")
      (node (ref "U$10") (pin "A14") (pinfunction "A14/DAC_A14") (pintype "bidirectional"))
    )
    (net (code "89") (name "unconnected-(U$10-Pad2)") (class "Default")
      (node (ref "U$10") (pin "2") (pinfunction "2_2") (pintype "bidirectional"))
    )
    (net (code "90") (name "unconnected-(U$10-PadA10)") (class "Default")
      (node (ref "U$10") (pin "A10") (pinfunction "A10_A10") (pintype "bidirectional"))
    )
    (net (code "91") (name "unconnected-(U$10-PadA11)") (class "Default")
      (node (ref "U$10") (pin "A11") (pinfunction "A11_A11") (pintype "bidirectional"))
    )
    (net (code "92") (name "unconnected-(U$10-PadPGM)") (class "Default")
      (node (ref "U$10") (pin "PGM") (pinfunction "PGM_PGM") (pintype "bidirectional"))
    )
    (net (code "93") (name "unconnected-(X1-CARD_DETECT1-PadCD2)") (class "Default")
      (node (ref "X1") (pin "CD2") (pinfunction "CARD_DETECT1_CD2") (pintype "passive"))
    )
    (net (code "94") (name "unconnected-(X1-DAT1-Pad8)") (class "Default")
      (node (ref "X1") (pin "8") (pinfunction "DAT1_8") (pintype "bidirectional"))
    )
    (net (code "95") (name "unconnected-(X1-DAT2-Pad1)") (class "Default")
      (node (ref "X1") (pin "1") (pinfunction "DAT2_1") (pintype "bidirectional"))
    )
    (net (code "96") (name "unconnected-(X2D-S-Pad12)") (class "Default")
      (node (ref "X2") (pin "12") (pinfunction "S_12") (pintype "passive"))
    )
    (net (code "97") (name "unconnected-(X2E-S-Pad13)") (class "Default")
      (node (ref "X2") (pin "13") (pinfunction "S_13") (pintype "passive"))
    )
    (net (code "98") (name "unconnected-(X2H-S-Pad16)") (class "Default")
      (node (ref "X2") (pin "16") (pinfunction "S_16") (pintype "passive"))
    )
    (net (code "99") (name "unconnected-(X2J-S-Pad18)") (class "Default")
      (node (ref "X2") (pin "18") (pinfunction "S_18") (pintype "passive"))
    )
    (net (code "100") (name "unconnected-(X2K-S-Pad19)") (class "Default")
      (node (ref "X2") (pin "19") (pinfunction "S_19") (pintype "passive"))
    )
    (net (code "101") (name "unconnected-(X2M-S-Pad20)") (class "Default")
      (node (ref "X2") (pin "20") (pinfunction "S_20") (pintype "passive"))
    )
    (net (code "102") (name "unconnected-(X2N-S-Pad21)") (class "Default")
      (node (ref "X2") (pin "21") (pinfunction "S_21") (pintype "passive"))
    )
    (net (code "103") (name "unconnected-(X2O-S-Pad22)") (class "Default")
      (node (ref "X2") (pin "22") (pinfunction "S_22") (pintype "passive"))
    )
    (net (code "104") (name "unconnected-(X2P-S-Pad23)") (class "Default")
      (node (ref "X2") (pin "23") (pinfunction "S_23") (pintype "passive"))
    )
    (net (code "105") (name "unconnected-(X2Q-S-Pad24)") (class "Default")
      (node (ref "X2") (pin "24") (pinfunction "S_24") (pintype "passive"))
    )
    (net (code "106") (name "unconnected-(X2T-S-Pad5)") (class "Default")
      (node (ref "X2") (pin "5") (pinfunction "S_5") (pintype "passive"))
    )
    (net (code "107") (name "unconnected-(X2U-S-Pad6)") (class "Default")
      (node (ref "X2") (pin "6") (pinfunction "S_6") (pintype "passive"))
    )
    (net (code "108") (name "unconnected-(X2V-S-Pad7)") (class "Default")
      (node (ref "X2") (pin "7") (pinfunction "S_7") (pintype "passive"))
    )
    (net (code "109") (name "unconnected-(X2W-S-Pad8)") (class "Default")
      (node (ref "X2") (pin "8") (pinfunction "S_8") (pintype "passive"))
    )
    (net (code "110") (name "unconnected-(X3D-S-Pad12)") (class "Default")
      (node (ref "X3") (pin "12") (pinfunction "S_12") (pintype "passive"))
    )
    (net (code "111") (name "unconnected-(X3E-S-Pad13)") (class "Default")
      (node (ref "X3") (pin "13") (pinfunction "S_13") (pintype "passive"))
    )
    (net (code "112") (name "unconnected-(X3H-S-Pad16)") (class "Default")
      (node (ref "X3") (pin "16") (pinfunction "S_16") (pintype "passive"))
    )
    (net (code "113") (name "unconnected-(X3J-S-Pad18)") (class "Default")
      (node (ref "X3") (pin "18") (pinfunction "S_18") (pintype "passive"))
    )
    (net (code "114") (name "unconnected-(X3K-S-Pad19)") (class "Default")
      (node (ref "X3") (pin "19") (pinfunction "S_19") (pintype "passive"))
    )
    (net (code "115") (name "unconnected-(X3M-S-Pad20)") (class "Default")
      (node (ref "X3") (pin "20") (pinfunction "S_20") (pintype "passive"))
    )
    (net (code "116") (name "unconnected-(X3N-S-Pad21)") (class "Default")
      (node (ref "X3") (pin "21") (pinfunction "S_21") (pintype "passive"))
    )
    (net (code "117") (name "unconnected-(X3O-S-Pad22)") (class "Default")
      (node (ref "X3") (pin "22") (pinfunction "S_22") (pintype "passive"))
    )
    (net (code "118") (name "unconnected-(X3P-S-Pad23)") (class "Default")
      (node (ref "X3") (pin "23") (pinfunction "S_23") (pintype "passive"))
    )
    (net (code "119") (name "unconnected-(X3Q-S-Pad24)") (class "Default")
      (node (ref "X3") (pin "24") (pinfunction "S_24") (pintype "passive"))
    )
    (net (code "120") (name "unconnected-(X3T-S-Pad5)") (class "Default")
      (node (ref "X3") (pin "5") (pinfunction "S_5") (pintype "passive"))
    )
    (net (code "121") (name "unconnected-(X3U-S-Pad6)") (class "Default")
      (node (ref "X3") (pin "6") (pinfunction "S_6") (pintype "passive"))
    )
    (net (code "122") (name "unconnected-(X3V-S-Pad7)") (class "Default")
      (node (ref "X3") (pin "7") (pinfunction "S_7") (pintype "passive"))
    )
    (net (code "123") (name "unconnected-(X3W-S-Pad8)") (class "Default")
      (node (ref "X3") (pin "8") (pinfunction "S_8") (pintype "passive"))
    )
  )
)
